# CoreBoard1.net
KiCad netlist of a schematic drawn in Altium Designer
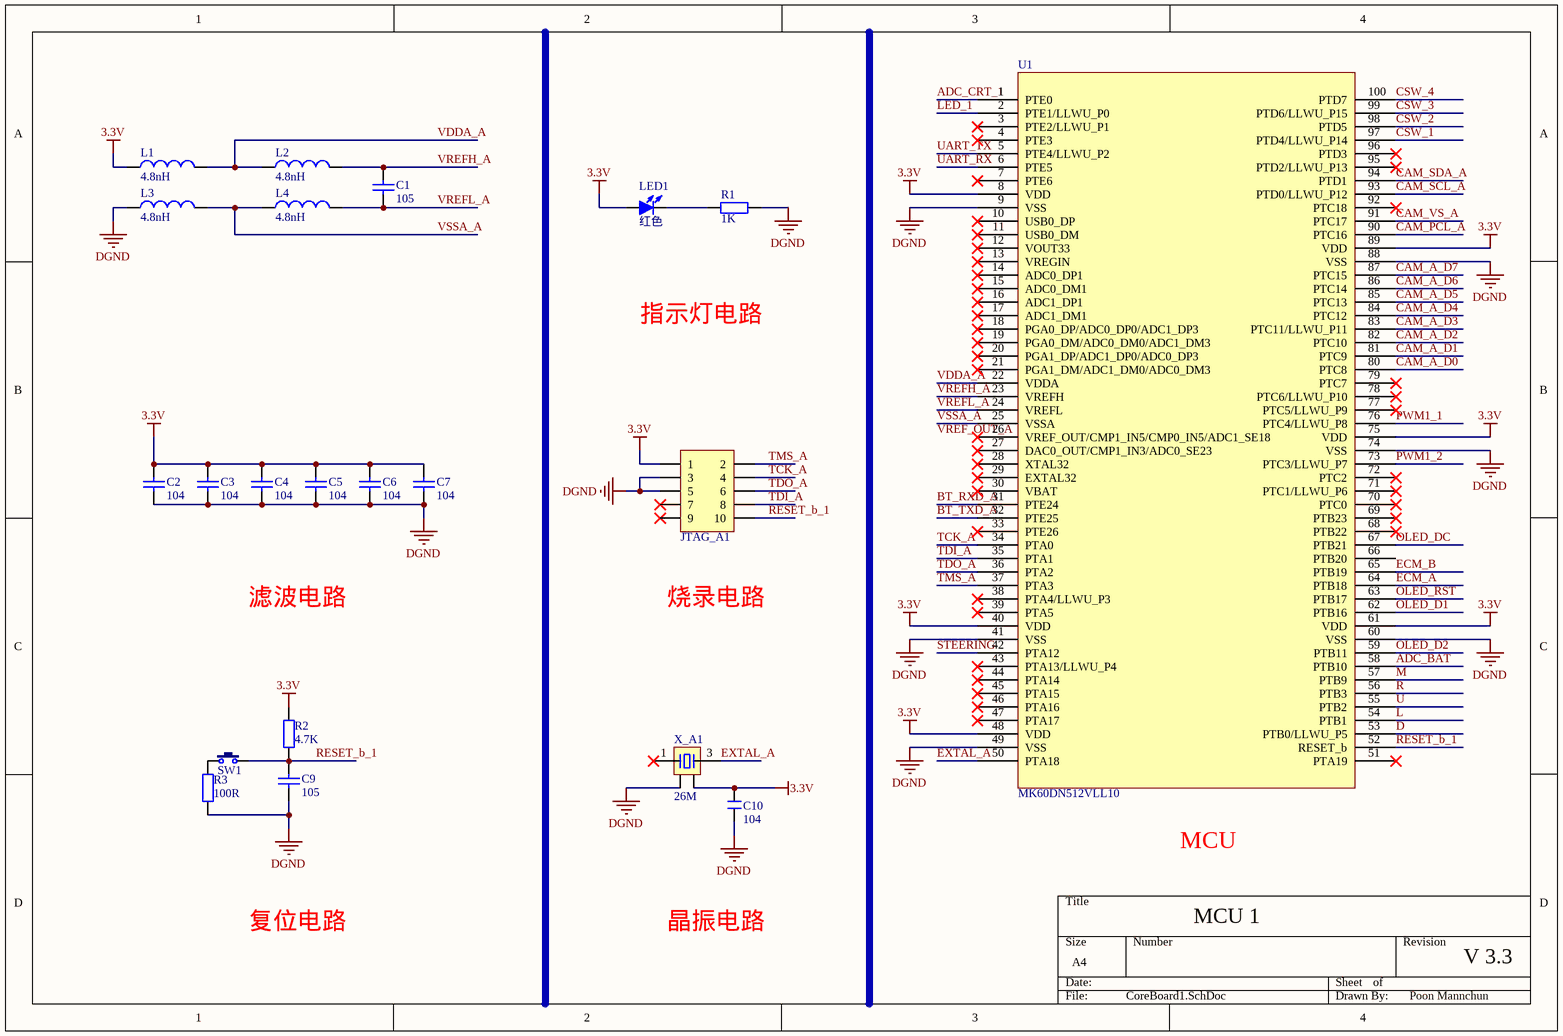
[diagram p0: CoreBoard1.SchDoc]

(export (version "E")
  (design (tool "Eeschema 10.0.6"))
  (components
    (comp (ref "C1")
      (value "105")
      (footprint "C 0805_L")
      (description "Capacitor")
      (fields (field (name "PUBLISHER") "Altium Limited"))
      (libsource (lib "6-MK60DN512VLL10核心板") (part "CAP"))
    )
    (comp (ref "C2")
      (value "104")
      (footprint "C 0805_L")
      (description "Capacitor")
      (fields (field (name "PUBLISHER") "Altium Limited"))
      (libsource (lib "6-MK60DN512VLL10核心板") (part "CAP"))
    )
    (comp (ref "C3")
      (value "104")
      (footprint "C 0805_L")
      (description "Capacitor")
      (fields (field (name "PUBLISHER") "Altium Limited"))
      (libsource (lib "6-MK60DN512VLL10核心板") (part "CAP"))
    )
    (comp (ref "C4")
      (value "104")
      (footprint "C 0805_L")
      (description "Capacitor")
      (fields (field (name "PUBLISHER") "Altium Limited"))
      (libsource (lib "6-MK60DN512VLL10核心板") (part "CAP"))
    )
    (comp (ref "C5")
      (value "104")
      (footprint "C 0805_L")
      (description "Capacitor")
      (fields (field (name "PUBLISHER") "Altium Limited"))
      (libsource (lib "6-MK60DN512VLL10核心板") (part "CAP"))
    )
    (comp (ref "C6")
      (value "104")
      (footprint "C 0805_L")
      (description "Capacitor")
      (fields (field (name "PUBLISHER") "Altium Limited"))
      (libsource (lib "6-MK60DN512VLL10核心板") (part "CAP"))
    )
    (comp (ref "C7")
      (value "104")
      (footprint "C 0805_L")
      (description "Capacitor")
      (fields (field (name "PUBLISHER") "Altium Limited"))
      (libsource (lib "6-MK60DN512VLL10核心板") (part "CAP"))
    )
    (comp (ref "C9")
      (value "105")
      (footprint "C 0805_L")
      (description "Capacitor")
      (fields (field (name "PUBLISHER") "Altium Limited"))
      (libsource (lib "6-MK60DN512VLL10核心板") (part "CAP"))
    )
    (comp (ref "C10")
      (value "104")
      (footprint "C 0805")
      (description "无极性贴片电容")
      (fields (field (name "版权归属") "源创客"))
      (libsource (lib "电阻-电容-电感") (part "C"))
    )
    (comp (ref "JTAG_A1")
      (value "Header 5X2")
      (footprint "HDR-5X2")
      (description "5*2P接插件")
      (fields (field (name "版权归属") "源创客"))
      (libsource (lib "接插件") (part "Header 5X2"))
    )
    (comp (ref "L1")
      (value "4.8nH")
      (footprint "L 0805")
      (description "Inductor")
      (fields (field (name "PUBLISHER") "Altium Limited"))
      (libsource (lib "6-MK60DN512VLL10核心板") (part "Inductor"))
    )
    (comp (ref "L2")
      (value "4.8nH")
      (footprint "L 0805")
      (description "Inductor")
      (fields (field (name "PUBLISHER") "Altium Limited"))
      (libsource (lib "6-MK60DN512VLL10核心板") (part "Inductor"))
    )
    (comp (ref "L3")
      (value "4.8nH")
      (footprint "L 0805")
      (description "Inductor")
      (fields (field (name "PUBLISHER") "Altium Limited"))
      (libsource (lib "6-MK60DN512VLL10核心板") (part "Inductor"))
    )
    (comp (ref "L4")
      (value "4.8nH")
      (footprint "L 0805")
      (description "Inductor")
      (fields (field (name "PUBLISHER") "Altium Limited"))
      (libsource (lib "6-MK60DN512VLL10核心板") (part "Inductor"))
    )
    (comp (ref "LED1")
      (value "红色")
      (footprint "LED 0805B")
      (description "贴片LED")
      (fields (field (name "版权归属") "源创客"))
      (libsource (lib "LED") (part "LED-SMD"))
    )
    (comp (ref "R1")
      (value "1K")
      (footprint "R 0805_L")
      (description "Resistor")
      (fields (field (name "PUBLISHER") "Altium Limited"))
      (libsource (lib "") (part "Res2_1"))
    )
    (comp (ref "R2")
      (value "4.7K")
      (footprint "R 0805_L")
      (description "Resistor")
      (fields (field (name "PUBLISHER") "Altium Limited"))
      (libsource (lib "6-MK60DN512VLL10核心板") (part "Res2"))
    )
    (comp (ref "R3")
      (value "100R")
      (footprint "R 0805_L")
      (description "Resistor")
      (fields (field (name "PUBLISHER") "Altium Limited"))
      (libsource (lib "6-MK60DN512VLL10核心板") (part "Res2"))
    )
    (comp (ref "SW1")
      (value "3x6x5")
      (footprint "TSW SMD-3*6*2.5")
      (description "3x6轻触开关")
      (fields (field (name "版权归属") "源创客"))
      (libsource (lib "按键-开关") (part "TSW 3x6"))
    )
    (comp (ref "U1")
      (value "MK60DN512VLL10")
      (footprint "LQFP100 14x14_N")
      (description "MK60DN512ZVLL10")
      (libsource (lib "6-MK60DN512VLL10核心板") (part "MK60DN512ZVLQ10"))
    )
    (comp (ref "X_A1")
      (value "26M")
      (footprint "OSC 5032-4P")
      (description "4脚晶振")
      (fields (field (name "版权归属") "源创客"))
      (libsource (lib "保险丝-晶振") (part "XTAL-4"))
    )
  )
  (nets
    (net (code "1") (name "/ADC_BAT") (class "Default")
      (node (ref "U1") (pin "58") (pinfunction "PTB10_58") (pintype "passive"))
    )
    (net (code "2") (name "/ADC_CRT_1") (class "Default")
      (node (ref "U1") (pin "1") (pinfunction "PTE0_1") (pintype "passive"))
    )
    (net (code "3") (name "/BT_RXD_A") (class "Default")
      (node (ref "U1") (pin "31") (pinfunction "PTE24_31") (pintype "passive"))
    )
    (net (code "4") (name "/BT_TXD_A") (class "Default")
      (node (ref "U1") (pin "32") (pinfunction "PTE25_32") (pintype "passive"))
    )
    (net (code "5") (name "/CAM_A_D0") (class "Default")
      (node (ref "U1") (pin "80") (pinfunction "PTC8_80") (pintype "passive"))
    )
    (net (code "6") (name "/CAM_A_D1") (class "Default")
      (node (ref "U1") (pin "81") (pinfunction "PTC9_81") (pintype "passive"))
    )
    (net (code "7") (name "/CAM_A_D2") (class "Default")
      (node (ref "U1") (pin "82") (pinfunction "PTC10_82") (pintype "passive"))
    )
    (net (code "8") (name "/CAM_A_D3") (class "Default")
      (node (ref "U1") (pin "83") (pinfunction "PTC11/LLWU_P11_83") (pintype "passive"))
    )
    (net (code "9") (name "/CAM_A_D4") (class "Default")
      (node (ref "U1") (pin "84") (pinfunction "PTC12_84") (pintype "passive"))
    )
    (net (code "10") (name "/CAM_A_D5") (class "Default")
      (node (ref "U1") (pin "85") (pinfunction "PTC13_85") (pintype "passive"))
    )
    (net (code "11") (name "/CAM_A_D6") (class "Default")
      (node (ref "U1") (pin "86") (pinfunction "PTC14_86") (pintype "passive"))
    )
    (net (code "12") (name "/CAM_A_D7") (class "Default")
      (node (ref "U1") (pin "87") (pinfunction "PTC15_87") (pintype "passive"))
    )
    (net (code "13") (name "/CAM_PCL_A") (class "Default")
      (node (ref "U1") (pin "90") (pinfunction "PTC16_90") (pintype "passive"))
    )
    (net (code "14") (name "/CAM_SCL_A") (class "Default")
      (node (ref "U1") (pin "93") (pinfunction "PTD0/LLWU_P12_93") (pintype "passive"))
    )
    (net (code "15") (name "/CAM_SDA_A") (class "Default")
      (node (ref "U1") (pin "94") (pinfunction "PTD1_94") (pintype "passive"))
    )
    (net (code "16") (name "/CAM_VS_A") (class "Default")
      (node (ref "U1") (pin "91") (pinfunction "PTC17_91") (pintype "passive"))
    )
    (net (code "17") (name "/CSW_1") (class "Default")
      (node (ref "U1") (pin "97") (pinfunction "PTD4/LLWU_P14_97") (pintype "passive"))
    )
    (net (code "18") (name "/CSW_2") (class "Default")
      (node (ref "U1") (pin "98") (pinfunction "PTD5_98") (pintype "passive"))
    )
    (net (code "19") (name "/CSW_3") (class "Default")
      (node (ref "U1") (pin "99") (pinfunction "PTD6/LLWU_P15_99") (pintype "passive"))
    )
    (net (code "20") (name "/CSW_4") (class "Default")
      (node (ref "U1") (pin "100") (pinfunction "PTD7_100") (pintype "passive"))
    )
    (net (code "21") (name "/D") (class "Default")
      (node (ref "U1") (pin "53") (pinfunction "PTB0/LLWU_P5_53") (pintype "passive"))
    )
    (net (code "22") (name "/ECM_A") (class "Default")
      (node (ref "U1") (pin "64") (pinfunction "PTB18_64") (pintype "passive"))
    )
    (net (code "23") (name "/ECM_B") (class "Default")
      (node (ref "U1") (pin "65") (pinfunction "PTB19_65") (pintype "passive"))
    )
    (net (code "24") (name "/EXTAL_A") (class "Default")
      (node (ref "U1") (pin "50") (pinfunction "PTA18_50") (pintype "passive"))
      (node (ref "X_A1") (pin "3") (pinfunction "3_3") (pintype "passive"))
    )
    (net (code "25") (name "/L") (class "Default")
      (node (ref "U1") (pin "54") (pinfunction "PTB1_54") (pintype "passive"))
    )
    (net (code "26") (name "/LED_1") (class "Default")
      (node (ref "U1") (pin "2") (pinfunction "PTE1/LLWU_P0_2") (pintype "passive"))
    )
    (net (code "27") (name "/M") (class "Default")
      (node (ref "U1") (pin "57") (pinfunction "PTB9_57") (pintype "passive"))
    )
    (net (code "28") (name "/OLED_D1") (class "Default")
      (node (ref "U1") (pin "62") (pinfunction "PTB16_62") (pintype "passive"))
    )
    (net (code "29") (name "/OLED_D2") (class "Default")
      (node (ref "U1") (pin "59") (pinfunction "PTB11_59") (pintype "passive"))
    )
    (net (code "30") (name "/OLED_DC") (class "Default")
      (node (ref "U1") (pin "67") (pinfunction "PTB21_67") (pintype "passive"))
    )
    (net (code "31") (name "/OLED_RST") (class "Default")
      (node (ref "U1") (pin "63") (pinfunction "PTB17_63") (pintype "passive"))
    )
    (net (code "32") (name "/PWM1_1") (class "Default")
      (node (ref "U1") (pin "76") (pinfunction "PTC4/LLWU_P8_76") (pintype "passive"))
    )
    (net (code "33") (name "/PWM1_2") (class "Default")
      (node (ref "U1") (pin "73") (pinfunction "PTC3/LLWU_P7_73") (pintype "passive"))
    )
    (net (code "34") (name "/R") (class "Default")
      (node (ref "U1") (pin "56") (pinfunction "PTB3_56") (pintype "passive"))
    )
    (net (code "35") (name "/RESET_b_1") (class "Default")
      (node (ref "C9") (pin "2") (pinfunction "2_2") (pintype "passive"))
      (node (ref "JTAG_A1") (pin "10") (pinfunction "10_10") (pintype "passive"))
      (node (ref "R2") (pin "1") (pinfunction "1_1") (pintype "passive"))
      (node (ref "SW1") (pin "2") (pinfunction "2_2") (pintype "passive"))
      (node (ref "U1") (pin "52") (pinfunction "RESET_b_52") (pintype "passive"))
    )
    (net (code "36") (name "/STEERING") (class "Default")
      (node (ref "U1") (pin "42") (pinfunction "PTA12_42") (pintype "passive"))
    )
    (net (code "37") (name "/TCK_A") (class "Default")
      (node (ref "JTAG_A1") (pin "4") (pinfunction "4_4") (pintype "passive"))
      (node (ref "U1") (pin "34") (pinfunction "PTA0_34") (pintype "passive"))
    )
    (net (code "38") (name "/TDI_A") (class "Default")
      (node (ref "JTAG_A1") (pin "8") (pinfunction "8_8") (pintype "passive"))
      (node (ref "U1") (pin "35") (pinfunction "PTA1_35") (pintype "passive"))
    )
    (net (code "39") (name "/TDO_A") (class "Default")
      (node (ref "JTAG_A1") (pin "6") (pinfunction "6_6") (pintype "passive"))
      (node (ref "U1") (pin "36") (pinfunction "PTA2_36") (pintype "passive"))
    )
    (net (code "40") (name "/TMS_A") (class "Default")
      (node (ref "JTAG_A1") (pin "2") (pinfunction "2_2") (pintype "passive"))
      (node (ref "U1") (pin "37") (pinfunction "PTA3_37") (pintype "passive"))
    )
    (net (code "41") (name "/U") (class "Default")
      (node (ref "U1") (pin "55") (pinfunction "PTB2_55") (pintype "passive"))
    )
    (net (code "42") (name "/UART_RX") (class "Default")
      (node (ref "U1") (pin "6") (pinfunction "PTE5_6") (pintype "passive"))
    )
    (net (code "43") (name "/UART_TX") (class "Default")
      (node (ref "U1") (pin "5") (pinfunction "PTE4/LLWU_P2_5") (pintype "passive"))
    )
    (net (code "44") (name "/VDDA_A") (class "Default")
      (node (ref "L1") (pin "2") (pinfunction "2_2") (pintype "passive"))
      (node (ref "L2") (pin "1") (pinfunction "1_1") (pintype "passive"))
      (node (ref "U1") (pin "22") (pinfunction "VDDA_22") (pintype "passive"))
    )
    (net (code "45") (name "/VREFH_A") (class "Default")
      (node (ref "C1") (pin "2") (pinfunction "2_2") (pintype "passive"))
      (node (ref "L2") (pin "2") (pinfunction "2_2") (pintype "passive"))
      (node (ref "U1") (pin "23") (pinfunction "VREFH_23") (pintype "passive"))
    )
    (net (code "46") (name "/VREFL_A") (class "Default")
      (node (ref "C1") (pin "1") (pinfunction "1_1") (pintype "passive"))
      (node (ref "L4") (pin "2") (pinfunction "2_2") (pintype "passive"))
      (node (ref "U1") (pin "24") (pinfunction "VREFL_24") (pintype "passive"))
    )
    (net (code "48") (name "/VSSA_A") (class "Default")
      (node (ref "L3") (pin "2") (pinfunction "2_2") (pintype "passive"))
      (node (ref "L4") (pin "1") (pinfunction "1_1") (pintype "passive"))
      (node (ref "U1") (pin "25") (pinfunction "VSSA_25") (pintype "passive"))
    )
    (net (code "49") (name "3.3V") (class "Default")
      (node (ref "C10") (pin "2") (pinfunction "2_2") (pintype "passive"))
      (node (ref "C2") (pin "2") (pinfunction "2_2") (pintype "passive"))
      (node (ref "C3") (pin "2") (pinfunction "2_2") (pintype "passive"))
      (node (ref "C4") (pin "2") (pinfunction "2_2") (pintype "passive"))
      (node (ref "C5") (pin "2") (pinfunction "2_2") (pintype "passive"))
      (node (ref "C6") (pin "2") (pinfunction "2_2") (pintype "passive"))
      (node (ref "C7") (pin "2") (pinfunction "2_2") (pintype "passive"))
      (node (ref "JTAG_A1") (pin "1") (pinfunction "1_1") (pintype "passive"))
      (node (ref "L1") (pin "1") (pinfunction "1_1") (pintype "passive"))
      (node (ref "LED1") (pin "1") (pinfunction "A_1") (pintype "passive"))
      (node (ref "R2") (pin "2") (pinfunction "2_2") (pintype "passive"))
      (node (ref "U1") (pin "40") (pinfunction "VDD_40") (pintype "passive"))
      (node (ref "U1") (pin "48") (pinfunction "VDD_48") (pintype "passive"))
      (node (ref "U1") (pin "61") (pinfunction "VDD_61") (pintype "passive"))
      (node (ref "U1") (pin "75") (pinfunction "VDD_75") (pintype "passive"))
      (node (ref "U1") (pin "8") (pinfunction "VDD_8") (pintype "passive"))
      (node (ref "U1") (pin "89") (pinfunction "VDD_89") (pintype "passive"))
      (node (ref "X_A1") (pin "4") (pinfunction "4_4") (pintype "passive"))
    )
    (net (code "50") (name "DGND") (class "Default")
      (node (ref "C10") (pin "1") (pinfunction "1_1") (pintype "passive"))
      (node (ref "C2") (pin "1") (pinfunction "1_1") (pintype "passive"))
      (node (ref "C3") (pin "1") (pinfunction "1_1") (pintype "passive"))
      (node (ref "C4") (pin "1") (pinfunction "1_1") (pintype "passive"))
      (node (ref "C5") (pin "1") (pinfunction "1_1") (pintype "passive"))
      (node (ref "C6") (pin "1") (pinfunction "1_1") (pintype "passive"))
      (node (ref "C7") (pin "1") (pinfunction "1_1") (pintype "passive"))
      (node (ref "C9") (pin "1") (pinfunction "1_1") (pintype "passive"))
      (node (ref "JTAG_A1") (pin "3") (pinfunction "3_3") (pintype "passive"))
      (node (ref "JTAG_A1") (pin "5") (pinfunction "5_5") (pintype "passive"))
      (node (ref "L3") (pin "1") (pinfunction "1_1") (pintype "passive"))
      (node (ref "R1") (pin "2") (pinfunction "2_2") (pintype "passive"))
      (node (ref "R3") (pin "1") (pinfunction "1_1") (pintype "passive"))
      (node (ref "U1") (pin "41") (pinfunction "VSS_41") (pintype "passive"))
      (node (ref "U1") (pin "49") (pinfunction "VSS_49") (pintype "passive"))
      (node (ref "U1") (pin "60") (pinfunction "VSS_60") (pintype "passive"))
      (node (ref "U1") (pin "74") (pinfunction "VSS_74") (pintype "passive"))
      (node (ref "U1") (pin "88") (pinfunction "VSS_88") (pintype "passive"))
      (node (ref "U1") (pin "9") (pinfunction "VSS_9") (pintype "passive"))
      (node (ref "X_A1") (pin "2") (pinfunction "2_2") (pintype "passive"))
    )
    (net (code "51") (name "Net-(LED1-K)") (class "Default")
      (node (ref "LED1") (pin "2") (pinfunction "K_2") (pintype "passive"))
      (node (ref "R1") (pin "1") (pinfunction "1_1") (pintype "passive"))
    )
    (net (code "52") (name "Net-(R3-Pad2)") (class "Default")
      (node (ref "R3") (pin "2") (pinfunction "2_2") (pintype "passive"))
      (node (ref "SW1") (pin "1") (pinfunction "1_1") (pintype "passive"))
    )
    (net (code "53") (name "unconnected-(JTAG_A1-Pad7)") (class "Default")
      (node (ref "JTAG_A1") (pin "7") (pinfunction "7_7") (pintype "passive+no_connect"))
    )
    (net (code "54") (name "unconnected-(JTAG_A1-Pad9)") (class "Default")
      (node (ref "JTAG_A1") (pin "9") (pinfunction "9_9") (pintype "passive+no_connect"))
    )
    (net (code "55") (name "unconnected-(U1-ADC0_DM1-Pad15)") (class "Default")
      (node (ref "U1") (pin "15") (pinfunction "ADC0_DM1_15") (pintype "passive+no_connect"))
    )
    (net (code "56") (name "unconnected-(U1-ADC0_DP1-Pad14)") (class "Default")
      (node (ref "U1") (pin "14") (pinfunction "ADC0_DP1_14") (pintype "passive+no_connect"))
    )
    (net (code "57") (name "unconnected-(U1-ADC1_DM1-Pad17)") (class "Default")
      (node (ref "U1") (pin "17") (pinfunction "ADC1_DM1_17") (pintype "passive+no_connect"))
    )
    (net (code "58") (name "unconnected-(U1-ADC1_DP1-Pad16)") (class "Default")
      (node (ref "U1") (pin "16") (pinfunction "ADC1_DP1_16") (pintype "passive+no_connect"))
    )
    (net (code "59") (name "unconnected-(U1-DAC0_OUT{slash}CMP1_IN3{slash}ADC0_SE23-Pad27)") (class "Default")
      (node (ref "U1") (pin "27") (pinfunction "DAC0_OUT/CMP1_IN3/ADC0_SE23_27") (pintype "passive+no_connect"))
    )
    (net (code "60") (name "unconnected-(U1-EXTAL32-Pad29)") (class "Default")
      (node (ref "U1") (pin "29") (pinfunction "EXTAL32_29") (pintype "passive+no_connect"))
    )
    (net (code "61") (name "unconnected-(U1-PGA0_DM{slash}ADC0_DM0{slash}ADC1_DM3-Pad19)") (class "Default")
      (node (ref "U1") (pin "19") (pinfunction "PGA0_DM/ADC0_DM0/ADC1_DM3_19") (pintype "passive+no_connect"))
    )
    (net (code "62") (name "unconnected-(U1-PGA0_DP{slash}ADC0_DP0{slash}ADC1_DP3-Pad18)") (class "Default")
      (node (ref "U1") (pin "18") (pinfunction "PGA0_DP/ADC0_DP0/ADC1_DP3_18") (pintype "passive+no_connect"))
    )
    (net (code "63") (name "unconnected-(U1-PGA1_DM{slash}ADC1_DM0{slash}ADC0_DM3-Pad21)") (class "Default")
      (node (ref "U1") (pin "21") (pinfunction "PGA1_DM/ADC1_DM0/ADC0_DM3_21") (pintype "passive+no_connect"))
    )
    (net (code "64") (name "unconnected-(U1-PGA1_DP{slash}ADC1_DP0{slash}ADC0_DP3-Pad20)") (class "Default")
      (node (ref "U1") (pin "20") (pinfunction "PGA1_DP/ADC1_DP0/ADC0_DP3_20") (pintype "passive+no_connect"))
    )
    (net (code "65") (name "unconnected-(U1-PTA4{slash}LLWU_P3-Pad38)") (class "Default")
      (node (ref "U1") (pin "38") (pinfunction "PTA4/LLWU_P3_38") (pintype "passive+no_connect"))
    )
    (net (code "66") (name "unconnected-(U1-PTA5-Pad39)") (class "Default")
      (node (ref "U1") (pin "39") (pinfunction "PTA5_39") (pintype "passive+no_connect"))
    )
    (net (code "67") (name "unconnected-(U1-PTA13{slash}LLWU_P4-Pad43)") (class "Default")
      (node (ref "U1") (pin "43") (pinfunction "PTA13/LLWU_P4_43") (pintype "passive+no_connect"))
    )
    (net (code "68") (name "unconnected-(U1-PTA14-Pad44)") (class "Default")
      (node (ref "U1") (pin "44") (pinfunction "PTA14_44") (pintype "passive+no_connect"))
    )
    (net (code "69") (name "unconnected-(U1-PTA15-Pad45)") (class "Default")
      (node (ref "U1") (pin "45") (pinfunction "PTA15_45") (pintype "passive+no_connect"))
    )
    (net (code "70") (name "unconnected-(U1-PTA16-Pad46)") (class "Default")
      (node (ref "U1") (pin "46") (pinfunction "PTA16_46") (pintype "passive+no_connect"))
    )
    (net (code "71") (name "unconnected-(U1-PTA17-Pad47)") (class "Default")
      (node (ref "U1") (pin "47") (pinfunction "PTA17_47") (pintype "passive+no_connect"))
    )
    (net (code "72") (name "unconnected-(U1-PTA19-Pad51)") (class "Default")
      (node (ref "U1") (pin "51") (pinfunction "PTA19_51") (pintype "passive+no_connect"))
    )
    (net (code "73") (name "unconnected-(U1-PTB20-Pad66)") (class "Default")
      (node (ref "U1") (pin "66") (pinfunction "PTB20_66") (pintype "passive"))
    )
    (net (code "74") (name "unconnected-(U1-PTB22-Pad68)") (class "Default")
      (node (ref "U1") (pin "68") (pinfunction "PTB22_68") (pintype "passive+no_connect"))
    )
    (net (code "75") (name "unconnected-(U1-PTB23-Pad69)") (class "Default")
      (node (ref "U1") (pin "69") (pinfunction "PTB23_69") (pintype "passive+no_connect"))
    )
    (net (code "76") (name "unconnected-(U1-PTC0-Pad70)") (class "Default")
      (node (ref "U1") (pin "70") (pinfunction "PTC0_70") (pintype "passive+no_connect"))
    )
    (net (code "77") (name "unconnected-(U1-PTC1{slash}LLWU_P6-Pad71)") (class "Default")
      (node (ref "U1") (pin "71") (pinfunction "PTC1/LLWU_P6_71") (pintype "passive+no_connect"))
    )
    (net (code "78") (name "unconnected-(U1-PTC2-Pad72)") (class "Default")
      (node (ref "U1") (pin "72") (pinfunction "PTC2_72") (pintype "passive+no_connect"))
    )
    (net (code "79") (name "unconnected-(U1-PTC5{slash}LLWU_P9-Pad77)") (class "Default")
      (node (ref "U1") (pin "77") (pinfunction "PTC5/LLWU_P9_77") (pintype "passive+no_connect"))
    )
    (net (code "80") (name "unconnected-(U1-PTC6{slash}LLWU_P10-Pad78)") (class "Default")
      (node (ref "U1") (pin "78") (pinfunction "PTC6/LLWU_P10_78") (pintype "passive+no_connect"))
    )
    (net (code "81") (name "unconnected-(U1-PTC7-Pad79)") (class "Default")
      (node (ref "U1") (pin "79") (pinfunction "PTC7_79") (pintype "passive+no_connect"))
    )
    (net (code "82") (name "unconnected-(U1-PTC18-Pad92)") (class "Default")
      (node (ref "U1") (pin "92") (pinfunction "PTC18_92") (pintype "passive+no_connect"))
    )
    (net (code "83") (name "unconnected-(U1-PTD2{slash}LLWU_P13-Pad95)") (class "Default")
      (node (ref "U1") (pin "95") (pinfunction "PTD2/LLWU_P13_95") (pintype "passive+no_connect"))
    )
    (net (code "84") (name "unconnected-(U1-PTD3-Pad96)") (class "Default")
      (node (ref "U1") (pin "96") (pinfunction "PTD3_96") (pintype "passive+no_connect"))
    )
    (net (code "85") (name "unconnected-(U1-PTE2{slash}LLWU_P1-Pad3)") (class "Default")
      (node (ref "U1") (pin "3") (pinfunction "PTE2/LLWU_P1_3") (pintype "passive+no_connect"))
    )
    (net (code "86") (name "unconnected-(U1-PTE3-Pad4)") (class "Default")
      (node (ref "U1") (pin "4") (pinfunction "PTE3_4") (pintype "passive+no_connect"))
    )
    (net (code "87") (name "unconnected-(U1-PTE6-Pad7)") (class "Default")
      (node (ref "U1") (pin "7") (pinfunction "PTE6_7") (pintype "passive+no_connect"))
    )
    (net (code "88") (name "unconnected-(U1-PTE26-Pad33)") (class "Default")
      (node (ref "U1") (pin "33") (pinfunction "PTE26_33") (pintype "passive+no_connect"))
    )
    (net (code "89") (name "unconnected-(U1-USB0_DM-Pad11)") (class "Default")
      (node (ref "U1") (pin "11") (pinfunction "USB0_DM_11") (pintype "passive+no_connect"))
    )
    (net (code "90") (name "unconnected-(U1-USB0_DP-Pad10)") (class "Default")
      (node (ref "U1") (pin "10") (pinfunction "USB0_DP_10") (pintype "passive+no_connect"))
    )
    (net (code "91") (name "unconnected-(U1-VBAT-Pad30)") (class "Default")
      (node (ref "U1") (pin "30") (pinfunction "VBAT_30") (pintype "passive+no_connect"))
    )
    (net (code "92") (name "unconnected-(U1-VOUT33-Pad12)") (class "Default")
      (node (ref "U1") (pin "12") (pinfunction "VOUT33_12") (pintype "passive+no_connect"))
    )
    (net (code "93") (name "unconnected-(U1-VREF_OUT{slash}CMP1_IN5{slash}CMP0_IN5{slash}ADC1_SE18-Pad26)") (class "Default")
      (node (ref "U1") (pin "26") (pinfunction "VREF_OUT/CMP1_IN5/CMP0_IN5/ADC1_SE18_26") (pintype "passive+no_connect"))
    )
    (net (code "94") (name "unconnected-(U1-VREGIN-Pad13)") (class "Default")
      (node (ref "U1") (pin "13") (pinfunction "VREGIN_13") (pintype "passive+no_connect"))
    )
    (net (code "95") (name "unconnected-(U1-XTAL32-Pad28)") (class "Default")
      (node (ref "U1") (pin "28") (pinfunction "XTAL32_28") (pintype "passive+no_connect"))
    )
    (net (code "96") (name "unconnected-(X_A1-Pad1)") (class "Default")
      (node (ref "X_A1") (pin "1") (pinfunction "1_1") (pintype "passive+no_connect"))
    )
  )
)
